# X3_Developer_RF.net
KiCad netlist of a schematic drawn in Altium Designer
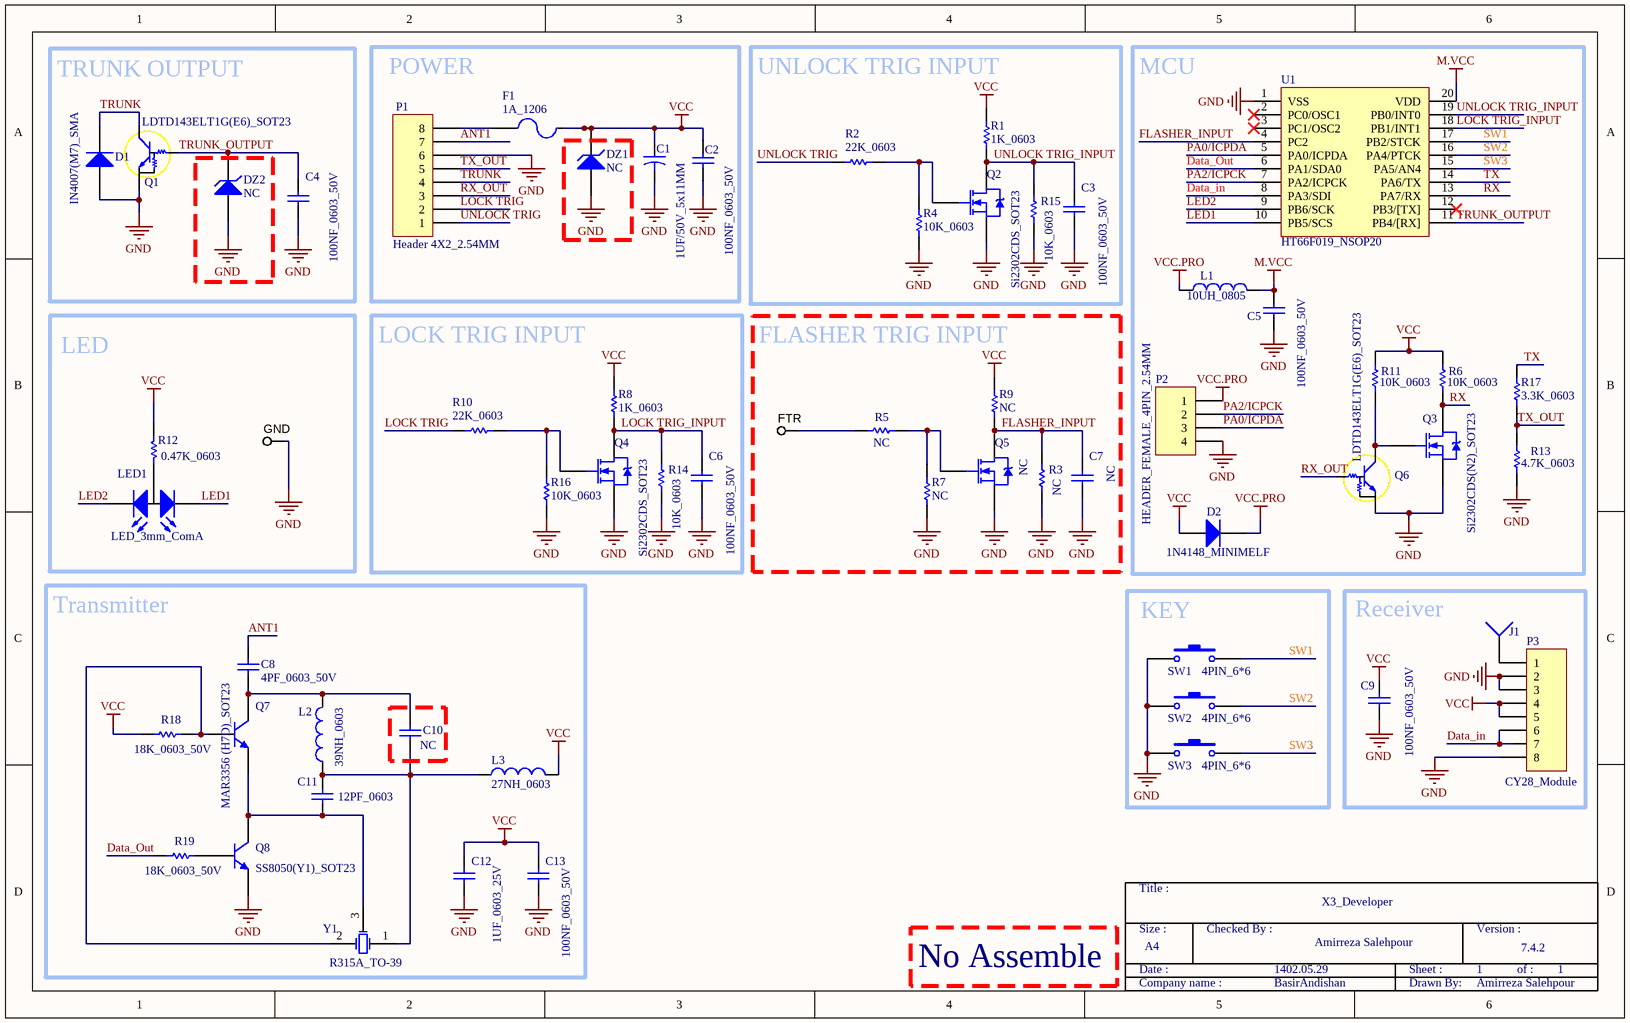
[diagram p0: X3_Developer_RF.SchDoc]

(export (version "E")
  (design (tool "Eeschema 10.0.6"))
  (components
    (comp (ref "C1")
      (value "1UF/50V_5x11MM")
      (footprint "Cap_5mm")
      (libsource (lib "Amir_Library") (part "Cap_Electrical"))
    )
    (comp (ref "C2")
      (value "100NF_0603_50V")
      (footprint "Cap_0603_Nominal")
      (libsource (lib "Saeed_New_Lib") (part "Cap"))
    )
    (comp (ref "C3")
      (value "100NF_0603_50V")
      (footprint "Cap_0603_Nominal")
      (libsource (lib "Saeed_New_Lib") (part "Cap"))
    )
    (comp (ref "C4")
      (value "100NF_0603_50V")
      (footprint "Cap_0603_Nominal")
      (libsource (lib "Saeed_New_Lib") (part "Cap"))
    )
    (comp (ref "C5")
      (value "100NF_0603_50V")
      (footprint "Cap_0603_Nominal")
      (libsource (lib "Saeed_New_Lib") (part "Cap"))
    )
    (comp (ref "C6")
      (value "100NF_0603_50V")
      (footprint "Cap_0603_Nominal")
      (libsource (lib "Saeed_New_Lib") (part "Cap"))
    )
    (comp (ref "C7")
      (value "NC")
      (footprint "Cap_0603_Nominal")
      (libsource (lib "Saeed_New_Lib") (part "Cap"))
    )
    (comp (ref "C8")
      (value "4PF_0603_50V")
      (footprint "Cap_0603_Nominal")
      (libsource (lib "Amir_Library") (part "Cap"))
    )
    (comp (ref "C9")
      (value "100NF_0603_50V")
      (footprint "Cap_0603_Nominal")
      (libsource (lib "Saeed_New_Lib") (part "Cap"))
    )
    (comp (ref "C10")
      (value "NC")
      (footprint "Cap_0603_Nominal")
      (libsource (lib "Amir_Library") (part "Cap"))
    )
    (comp (ref "C11")
      (value "12PF_0603")
      (footprint "Cap_0603_Nominal")
      (fields (field (name "Comment") "12PF_0603_50V"))
      (libsource (lib "Amir_Library") (part "Cap"))
    )
    (comp (ref "C12")
      (value "1UF_0603_25V")
      (footprint "Cap_0603_Nominal")
      (libsource (lib "Amir_Library") (part "Cap"))
    )
    (comp (ref "C13")
      (value "100NF_0603_50V")
      (footprint "Cap_0603_Nominal")
      (libsource (lib "Amir_Library") (part "Cap"))
    )
    (comp (ref "D1")
      (value "IN4007(M7)_SMA")
      (footprint "DIODE_SMA")
      (libsource (lib "My Shematic") (part "Diode"))
    )
    (comp (ref "D2")
      (value "1N4148_MINIMELF")
      (footprint "DIODE_MINIMELF")
      (libsource (lib "Amir_Library") (part "Diode"))
    )
    (comp (ref "DZ1")
      (value "NC")
      (footprint "Diode_ZENER_MINIMELF")
      (libsource (lib "Amir_Library") (part "Diode_Zener"))
    )
    (comp (ref "DZ2")
      (value "NC")
      (footprint "Diode_ZENER_MINIMELF")
      (libsource (lib "Amir_Library") (part "Diode_Zener"))
    )
    (comp (ref "F1")
      (value "1A_1206")
      (footprint "FUSE_1206_NOMINAL")
      (libsource (lib "Amir_Library") (part "FUSE"))
    )
    (comp (ref "FTR")
      (value "TESTPOINT_SMD")
      (footprint "TPSMD_D1")
      (fields (field (name "MANF") "MANF") (field (name "MANF_P#") "MANF_P#"))
      (libsource (lib "GTC Schematic") (part "TESTPOINT_SMD"))
    )
    (comp (ref "GND")
      (value "TESTPOINT_SMD")
      (footprint "TPSMD_D1")
      (fields (field (name "MANF") "MANF") (field (name "MANF_P#") "MANF_P#"))
      (libsource (lib "GTC Schematic") (part "TESTPOINT_SMD"))
    )
    (comp (ref "J1")
      (value "ANT")
      (footprint "PIN1")
      (description "Socket")
      (fields (field (name "PUBLISHER") "Altium Limited"))
      (libsource (lib "Miscellaneous Connectors") (part "Socket"))
    )
    (comp (ref "L1")
      (value "10UH_0805")
      (footprint "INDUCTOR_0805_Nominal")
      (libsource (lib "Saeed_New_Lib") (part "Inductor"))
    )
    (comp (ref "L2")
      (value "39NH_0603")
      (footprint "INDUCTOR_0603_NOMINAL")
      (libsource (lib "") (part "Inductor_1"))
    )
    (comp (ref "L3")
      (value "27NH_0603")
      (footprint "INDUCTOR_0603_NOMINAL")
      (libsource (lib "Amir_Library") (part "Inductor"))
    )
    (comp (ref "LED1")
      (value "LED_3mm_ComA")
      (footprint "LED_3mm_ComA")
      (libsource (lib "GTC Shem") (part "LED_ComA"))
    )
    (comp (ref "P1")
      (value "Header 4X2_2.54MM")
      (footprint "CON_2X4PIN")
      (description "Header, 4-Pin")
      (fields (field (name "PUBLISHER") "Altium Limited"))
      (libsource (lib "GTC Shem") (part "Header 8"))
    )
    (comp (ref "P2")
      (value "HEADER_FEMALE_4PIN_2.54MM")
      (footprint "HDR_F_1X4_2mm")
      (fields (field (name "PUBLISHER") "Altium Limited"))
      (libsource (lib "Miscellaneous Connectors") (part "Header 4"))
    )
    (comp (ref "P3")
      (value "CY28_Module")
      (footprint "RF_RXB6")
      (description "Receiver_315")
      (fields (field (name "PUBLISHER") "Altium Limited"))
      (libsource (lib "Amir_Library") (part "RXB6"))
    )
    (comp (ref "Q1")
      (value "LDTD143ELT1G(E6)_SOT23")
      (footprint "SOT23")
      (libsource (lib "My Shematic") (part "NPN_Digital"))
    )
    (comp (ref "Q2")
      (value "Si2302CDS_SOT23")
      (footprint "SOT23_MOSFET")
      (fields (field (name "PUBLISHER") "Altium Limited"))
      (libsource (lib "GTC Shem") (part "MOSFET_N"))
    )
    (comp (ref "Q3")
      (value "Si2302CDS(N2)_SOT23")
      (footprint "SOT23_MOSFET")
      (fields (field (name "PUBLISHER") "Altium Limited"))
      (libsource (lib "GTC Shem") (part "MOSFET_N"))
    )
    (comp (ref "Q4")
      (value "Si2302CDS_SOT23")
      (footprint "SOT23_MOSFET")
      (fields (field (name "PUBLISHER") "Altium Limited"))
      (libsource (lib "GTC Shem") (part "MOSFET_N"))
    )
    (comp (ref "Q5")
      (value "NC")
      (footprint "SOT23_MOSFET")
      (description "Si2302CDS_SOT23")
      (fields (field (name "PUBLISHER") "Altium Limited"))
      (libsource (lib "GTC Shem") (part "MOSFET_N"))
    )
    (comp (ref "Q6")
      (value "LDTD143ELT1G(E6)_SOT23")
      (footprint "SOT23")
      (libsource (lib "") (part "NPN_Digital_1"))
    )
    (comp (ref "Q7")
      (value "MAR3356 (H7D)_SOT23")
      (footprint "SOT23_BJT")
      (libsource (lib "Amir_Library") (part "NPN"))
    )
    (comp (ref "Q8")
      (value "SS8050(Y1)_SOT23")
      (footprint "SOT23_BJT")
      (libsource (lib "Amir_Library") (part "NPN"))
    )
    (comp (ref "R1")
      (value "1K_0603")
      (footprint "Res_0603_Nominal")
      (libsource (lib "My Shematic") (part "RES"))
    )
    (comp (ref "R2")
      (value "22K_0603")
      (footprint "Res_0603_Nominal")
      (libsource (lib "My Shematic") (part "RES"))
    )
    (comp (ref "R3") (value "NC") (footprint "Res_0603_Nominal") (libsource (lib "My Shematic") (part "RES")))
    (comp (ref "R4")
      (value "10K_0603")
      (footprint "Res_0603_Nominal")
      (libsource (lib "My Shematic") (part "RES"))
    )
    (comp (ref "R5") (value "NC") (footprint "Res_0603_Nominal") (libsource (lib "My Shematic") (part "RES")))
    (comp (ref "R6")
      (value "10K_0603")
      (footprint "Res_0603_Nominal")
      (libsource (lib "Amir_Library") (part "RES"))
    )
    (comp (ref "R7") (value "NC") (footprint "Res_0603_Nominal") (libsource (lib "My Shematic") (part "RES")))
    (comp (ref "R8")
      (value "1K_0603")
      (footprint "Res_0603_Nominal")
      (libsource (lib "My Shematic") (part "RES"))
    )
    (comp (ref "R9") (value "NC") (footprint "Res_0603_Nominal") (libsource (lib "My Shematic") (part "RES")))
    (comp (ref "R10")
      (value "22K_0603")
      (footprint "Res_0603_Nominal")
      (libsource (lib "My Shematic") (part "RES"))
    )
    (comp (ref "R11")
      (value "10K_0603")
      (footprint "Res_0603_Nominal")
      (libsource (lib "Amir_Library") (part "RES"))
    )
    (comp (ref "R12")
      (value "0.47K_0603")
      (footprint "Res_0603_Nominal")
      (libsource (lib "My Shematic") (part "RES"))
    )
    (comp (ref "R13")
      (value "4.7K_0603")
      (footprint "Res_0603_Nominal")
      (libsource (lib "Amir_Library") (part "RES"))
    )
    (comp (ref "R14")
      (value "10K_0603")
      (footprint "Res_0603_Nominal")
      (libsource (lib "My Shematic") (part "RES"))
    )
    (comp (ref "R15")
      (value "10K_0603")
      (footprint "Res_0603_Nominal")
      (libsource (lib "My Shematic") (part "RES"))
    )
    (comp (ref "R16")
      (value "10K_0603")
      (footprint "Res_0603_Nominal")
      (libsource (lib "My Shematic") (part "RES"))
    )
    (comp (ref "R17")
      (value "3.3K_0603")
      (footprint "Res_0603_Nominal")
      (libsource (lib "Amir_Library") (part "RES"))
    )
    (comp (ref "R18")
      (value "18K_0603_50V")
      (footprint "Res_0603_Nominal")
      (libsource (lib "Amir_Library") (part "RES"))
    )
    (comp (ref "R19")
      (value "18K_0603_50V")
      (footprint "Res_0603_Nominal")
      (libsource (lib "Amir_Library") (part "RES"))
    )
    (comp (ref "SW1")
      (value "4PIN_6*6")
      (footprint "SWITCH_DIP_6*6")
      (libsource (lib "My Shematic") (part "SW"))
    )
    (comp (ref "SW2")
      (value "4PIN_6*6")
      (footprint "SWITCH_DIP_6*6")
      (libsource (lib "Saeed_New_Lib") (part "SW_Right"))
    )
    (comp (ref "SW3")
      (value "4PIN_6*6")
      (footprint "SWITCH_DIP_6*6")
      (libsource (lib "Saeed_New_Lib") (part "SW_Right"))
    )
    (comp (ref "U1")
      (value "HT66F019_NSOP20")
      (footprint "NSOP20")
      (libsource (lib "GTC Shem") (part "HT66F019"))
    )
    (comp (ref "Y1")
      (value "R315A_TO-39")
      (footprint "CRYSTAL_TO39")
      (description "SAWFILTER")
      (libsource (lib "My Shematic") (part "Saw_Filter"))
    )
  )
  (nets
    (net (code "1") (name "/ANT1") (class "Default")
      (node (ref "C8") (pin "2") (pinfunction "2_2") (pintype "passive"))
      (node (ref "P1") (pin "7") (pinfunction "7_7") (pintype "passive"))
    )
    (net (code "2") (name "/Data_Out") (class "Default")
      (node (ref "R19") (pin "1") (pinfunction "1_1") (pintype "passive"))
      (node (ref "U1") (pin "6") (pinfunction "PA1/SDA0_6") (pintype "passive"))
    )
    (net (code "3") (name "/Data_in") (class "Default")
      (node (ref "P3") (pin "6") (pinfunction "6_6") (pintype "passive"))
      (node (ref "P3") (pin "7") (pinfunction "7_7") (pintype "passive"))
      (node (ref "U1") (pin "8") (pinfunction "PA3/SDI_8") (pintype "passive"))
    )
    (net (code "4") (name "/FLASHER_INPUT") (class "Default")
      (node (ref "C7") (pin "2") (pinfunction "2_2") (pintype "passive"))
      (node (ref "Q5") (pin "3") (pinfunction "D_3") (pintype "passive"))
      (node (ref "R3") (pin "1") (pinfunction "1_1") (pintype "passive"))
      (node (ref "R9") (pin "2") (pinfunction "2_2") (pintype "passive"))
      (node (ref "U1") (pin "4") (pinfunction "PC2_4") (pintype "passive"))
    )
    (net (code "5") (name "/LED1") (class "Default")
      (node (ref "LED1") (pin "2") (pinfunction "A2_2") (pintype "passive"))
      (node (ref "U1") (pin "10") (pinfunction "PB5/SCS_10") (pintype "passive"))
    )
    (net (code "6") (name "/LED2") (class "Default")
      (node (ref "LED1") (pin "1") (pinfunction "A1_1") (pintype "passive"))
      (node (ref "U1") (pin "9") (pinfunction "PB6/SCK_9") (pintype "passive"))
    )
    (net (code "7") (name "/LOCK TRIG") (class "Default")
      (node (ref "P1") (pin "2") (pinfunction "2_2") (pintype "passive"))
      (node (ref "R10") (pin "2") (pinfunction "2_2") (pintype "passive"))
    )
    (net (code "8") (name "/LOCK TRIG_INPUT") (class "Default")
      (node (ref "C6") (pin "2") (pinfunction "2_2") (pintype "passive"))
      (node (ref "Q4") (pin "3") (pinfunction "D_3") (pintype "passive"))
      (node (ref "R14") (pin "1") (pinfunction "1_1") (pintype "passive"))
      (node (ref "R8") (pin "2") (pinfunction "2_2") (pintype "passive"))
      (node (ref "U1") (pin "18") (pinfunction "PB1/INT1_18") (pintype "passive"))
    )
    (net (code "9") (name "/PA0{slash}ICPDA") (class "Default")
      (node (ref "P2") (pin "3") (pinfunction "3_3") (pintype "passive"))
      (node (ref "U1") (pin "5") (pinfunction "PA0/ICPDA_5") (pintype "passive"))
    )
    (net (code "10") (name "/PA2{slash}ICPCK") (class "Default")
      (node (ref "P2") (pin "2") (pinfunction "2_2") (pintype "passive"))
      (node (ref "U1") (pin "7") (pinfunction "PA2/ICPCK_7") (pintype "passive"))
    )
    (net (code "11") (name "/RX") (class "Default")
      (node (ref "Q3") (pin "3") (pinfunction "D_3") (pintype "passive"))
      (node (ref "R6") (pin "1") (pinfunction "1_1") (pintype "passive"))
      (node (ref "U1") (pin "13") (pinfunction "PA7/RX_13") (pintype "passive"))
    )
    (net (code "12") (name "/RX_OUT") (class "Default")
      (node (ref "P1") (pin "3") (pinfunction "3_3") (pintype "passive"))
      (node (ref "Q6") (pin "1") (pinfunction "B_1") (pintype "passive"))
    )
    (net (code "13") (name "/SW1") (class "Default")
      (node (ref "SW1") (pin "2") (pinfunction "2_2") (pintype "passive"))
      (node (ref "U1") (pin "17") (pinfunction "PB2/STCK_17") (pintype "passive"))
    )
    (net (code "14") (name "/SW2") (class "Default")
      (node (ref "SW2") (pin "2") (pinfunction "2_2") (pintype "passive"))
      (node (ref "U1") (pin "16") (pinfunction "PA4/PTCK_16") (pintype "passive"))
    )
    (net (code "15") (name "/SW3") (class "Default")
      (node (ref "SW3") (pin "2") (pinfunction "2_2") (pintype "passive"))
      (node (ref "U1") (pin "15") (pinfunction "PA5/AN4_15") (pintype "passive"))
    )
    (net (code "16") (name "/TRUNK") (class "Default")
      (node (ref "D1") (pin "2") (pinfunction "K_2") (pintype "passive"))
      (node (ref "P1") (pin "4") (pinfunction "4_4") (pintype "passive"))
      (node (ref "Q1") (pin "3") (pinfunction "C_3") (pintype "passive"))
    )
    (net (code "17") (name "/TRUNK_OUTPUT") (class "Default")
      (node (ref "C4") (pin "2") (pinfunction "2_2") (pintype "passive"))
      (node (ref "DZ2") (pin "2") (pinfunction "K_2") (pintype "passive"))
      (node (ref "Q1") (pin "1") (pinfunction "B_1") (pintype "passive"))
      (node (ref "U1") (pin "11") (pinfunction "PB4/[RX]_11") (pintype "passive"))
    )
    (net (code "18") (name "/TX") (class "Default")
      (node (ref "R17") (pin "1") (pinfunction "1_1") (pintype "passive"))
      (node (ref "U1") (pin "14") (pinfunction "PA6/TX_14") (pintype "passive"))
    )
    (net (code "19") (name "/TX_OUT") (class "Default")
      (node (ref "P1") (pin "5") (pinfunction "5_5") (pintype "passive"))
      (node (ref "R13") (pin "2") (pinfunction "2_2") (pintype "passive"))
      (node (ref "R17") (pin "2") (pinfunction "2_2") (pintype "passive"))
    )
    (net (code "20") (name "/UNLOCK TRIG") (class "Default")
      (node (ref "P1") (pin "1") (pinfunction "1_1") (pintype "passive"))
      (node (ref "R2") (pin "2") (pinfunction "2_2") (pintype "passive"))
    )
    (net (code "21") (name "/UNLOCK TRIG_INPUT") (class "Default")
      (node (ref "C3") (pin "2") (pinfunction "2_2") (pintype "passive"))
      (node (ref "Q2") (pin "3") (pinfunction "D_3") (pintype "passive"))
      (node (ref "R1") (pin "2") (pinfunction "2_2") (pintype "passive"))
      (node (ref "R15") (pin "1") (pinfunction "1_1") (pintype "passive"))
      (node (ref "U1") (pin "19") (pinfunction "PB0/INT0_19") (pintype "passive"))
    )
    (net (code "22") (name "GND") (class "Default")
      (node (ref "C1") (pin "2") (pinfunction "2_2") (pintype "passive"))
      (node (ref "C12") (pin "1") (pinfunction "1_1") (pintype "passive"))
      (node (ref "C13") (pin "1") (pinfunction "1_1") (pintype "passive"))
      (node (ref "C2") (pin "1") (pinfunction "1_1") (pintype "passive"))
      (node (ref "C3") (pin "1") (pinfunction "1_1") (pintype "passive"))
      (node (ref "C4") (pin "1") (pinfunction "1_1") (pintype "passive"))
      (node (ref "C5") (pin "1") (pinfunction "1_1") (pintype "passive"))
      (node (ref "C6") (pin "1") (pinfunction "1_1") (pintype "passive"))
      (node (ref "C7") (pin "1") (pinfunction "1_1") (pintype "passive"))
      (node (ref "C9") (pin "1") (pinfunction "1_1") (pintype "passive"))
      (node (ref "D1") (pin "1") (pinfunction "A_1") (pintype "passive"))
      (node (ref "DZ1") (pin "1") (pinfunction "A_1") (pintype "passive"))
      (node (ref "DZ2") (pin "1") (pinfunction "A_1") (pintype "passive"))
      (node (ref "GND") (pin "1") (pinfunction "1_1") (pintype "passive"))
      (node (ref "P1") (pin "6") (pinfunction "6_6") (pintype "passive"))
      (node (ref "P2") (pin "4") (pinfunction "4_4") (pintype "passive"))
      (node (ref "P3") (pin "2") (pinfunction "2_2") (pintype "passive"))
      (node (ref "P3") (pin "3") (pinfunction "3_3") (pintype "passive"))
      (node (ref "P3") (pin "8") (pinfunction "8_8") (pintype "passive"))
      (node (ref "Q1") (pin "2") (pinfunction "E_2") (pintype "passive"))
      (node (ref "Q2") (pin "2") (pinfunction "S_2") (pintype "passive"))
      (node (ref "Q3") (pin "2") (pinfunction "S_2") (pintype "passive"))
      (node (ref "Q4") (pin "2") (pinfunction "S_2") (pintype "passive"))
      (node (ref "Q5") (pin "2") (pinfunction "S_2") (pintype "passive"))
      (node (ref "Q6") (pin "2") (pinfunction "E_2") (pintype "passive"))
      (node (ref "Q8") (pin "2") (pinfunction "E_2") (pintype "passive"))
      (node (ref "R13") (pin "1") (pinfunction "1_1") (pintype "passive"))
      (node (ref "R14") (pin "2") (pinfunction "2_2") (pintype "passive"))
      (node (ref "R15") (pin "2") (pinfunction "2_2") (pintype "passive"))
      (node (ref "R16") (pin "2") (pinfunction "2_2") (pintype "passive"))
      (node (ref "R3") (pin "2") (pinfunction "2_2") (pintype "passive"))
      (node (ref "R4") (pin "2") (pinfunction "2_2") (pintype "passive"))
      (node (ref "R7") (pin "2") (pinfunction "2_2") (pintype "passive"))
      (node (ref "SW1") (pin "1") (pinfunction "1_1") (pintype "passive"))
      (node (ref "SW2") (pin "1") (pinfunction "1_1") (pintype "passive"))
      (node (ref "SW3") (pin "1") (pinfunction "1_1") (pintype "passive"))
      (node (ref "U1") (pin "1") (pinfunction "VSS_1") (pintype "passive"))
    )
    (net (code "23") (name "M.VCC") (class "Default")
      (node (ref "C5") (pin "2") (pinfunction "2_2") (pintype "passive"))
      (node (ref "L1") (pin "2") (pinfunction "2_2") (pintype "passive"))
      (node (ref "U1") (pin "20") (pinfunction "VDD_20") (pintype "passive"))
    )
    (net (code "24") (name "Net-(C10-Pad1)") (class "Default")
      (node (ref "C10") (pin "1") (pinfunction "1_1") (pintype "passive"))
      (node (ref "C11") (pin "2") (pinfunction "2_2") (pintype "passive"))
      (node (ref "L2") (pin "1") (pinfunction "1_1") (pintype "passive"))
      (node (ref "L3") (pin "2") (pinfunction "2_2") (pintype "passive"))
      (node (ref "Y1") (pin "1") (pinfunction "1_1") (pintype "passive"))
    )
    (net (code "25") (name "Net-(F1-Pad1)") (class "Default")
      (node (ref "F1") (pin "1") (pinfunction "1_1") (pintype "passive"))
      (node (ref "P1") (pin "8") (pinfunction "8_8") (pintype "passive"))
    )
    (net (code "26") (name "Net-(FTR-Pad1)") (class "Default")
      (node (ref "FTR") (pin "1") (pinfunction "1_1") (pintype "passive"))
      (node (ref "R5") (pin "2") (pinfunction "2_2") (pintype "passive"))
    )
    (net (code "27") (name "Net-(J1-Pad1)") (class "Default")
      (node (ref "J1") (pin "1") (pinfunction "1_1") (pintype "passive"))
      (node (ref "P3") (pin "1") (pinfunction "1_1") (pintype "passive"))
    )
    (net (code "28") (name "Net-(LED1-K)") (class "Default")
      (node (ref "LED1") (pin "3") (pinfunction "K_3") (pintype "passive"))
      (node (ref "R12") (pin "2") (pinfunction "2_2") (pintype "passive"))
    )
    (net (code "29") (name "Net-(Q2-G)") (class "Default")
      (node (ref "Q2") (pin "1") (pinfunction "G_1") (pintype "passive"))
      (node (ref "R2") (pin "1") (pinfunction "1_1") (pintype "passive"))
      (node (ref "R4") (pin "1") (pinfunction "1_1") (pintype "passive"))
    )
    (net (code "30") (name "Net-(Q3-G)") (class "Default")
      (node (ref "Q3") (pin "1") (pinfunction "G_1") (pintype "passive"))
      (node (ref "Q6") (pin "3") (pinfunction "C_3") (pintype "passive"))
      (node (ref "R11") (pin "1") (pinfunction "1_1") (pintype "passive"))
    )
    (net (code "31") (name "Net-(Q4-G)") (class "Default")
      (node (ref "Q4") (pin "1") (pinfunction "G_1") (pintype "passive"))
      (node (ref "R10") (pin "1") (pinfunction "1_1") (pintype "passive"))
      (node (ref "R16") (pin "1") (pinfunction "1_1") (pintype "passive"))
    )
    (net (code "32") (name "Net-(Q5-G)") (class "Default")
      (node (ref "Q5") (pin "1") (pinfunction "G_1") (pintype "passive"))
      (node (ref "R5") (pin "1") (pinfunction "1_1") (pintype "passive"))
      (node (ref "R7") (pin "1") (pinfunction "1_1") (pintype "passive"))
    )
    (net (code "33") (name "Net-(Q7-B)") (class "Default")
      (node (ref "Q7") (pin "1") (pinfunction "B_1") (pintype "passive"))
      (node (ref "R18") (pin "1") (pinfunction "1_1") (pintype "passive"))
      (node (ref "Y1") (pin "2") (pinfunction "2_2") (pintype "passive"))
    )
    (net (code "34") (name "Net-(Q7-C)") (class "Default")
      (node (ref "C10") (pin "2") (pinfunction "2_2") (pintype "passive"))
      (node (ref "C8") (pin "1") (pinfunction "1_1") (pintype "passive"))
      (node (ref "L2") (pin "2") (pinfunction "2_2") (pintype "passive"))
      (node (ref "Q7") (pin "3") (pinfunction "C_3") (pintype "passive"))
    )
    (net (code "35") (name "Net-(Q7-E)") (class "Default")
      (node (ref "C11") (pin "1") (pinfunction "1_1") (pintype "passive"))
      (node (ref "Q7") (pin "2") (pinfunction "E_2") (pintype "passive"))
      (node (ref "Q8") (pin "3") (pinfunction "C_3") (pintype "passive"))
      (node (ref "Y1") (pin "3") (pinfunction "3_3") (pintype "passive"))
    )
    (net (code "36") (name "Net-(Q8-B)") (class "Default")
      (node (ref "Q8") (pin "1") (pinfunction "B_1") (pintype "passive"))
      (node (ref "R19") (pin "2") (pinfunction "2_2") (pintype "passive"))
    )
    (net (code "37") (name "VCC") (class "Default")
      (node (ref "C1") (pin "1") (pinfunction "1_1") (pintype "passive"))
      (node (ref "C12") (pin "2") (pinfunction "2_2") (pintype "passive"))
      (node (ref "C13") (pin "2") (pinfunction "2_2") (pintype "passive"))
      (node (ref "C2") (pin "2") (pinfunction "2_2") (pintype "passive"))
      (node (ref "C9") (pin "2") (pinfunction "2_2") (pintype "passive"))
      (node (ref "D2") (pin "1") (pinfunction "A_1") (pintype "passive"))
      (node (ref "DZ1") (pin "2") (pinfunction "K_2") (pintype "passive"))
      (node (ref "F1") (pin "2") (pinfunction "2_2") (pintype "passive"))
      (node (ref "L3") (pin "1") (pinfunction "1_1") (pintype "passive"))
      (node (ref "P3") (pin "4") (pinfunction "4_4") (pintype "passive"))
      (node (ref "P3") (pin "5") (pinfunction "5_5") (pintype "passive"))
      (node (ref "R1") (pin "1") (pinfunction "1_1") (pintype "passive"))
      (node (ref "R11") (pin "2") (pinfunction "2_2") (pintype "passive"))
      (node (ref "R12") (pin "1") (pinfunction "1_1") (pintype "passive"))
      (node (ref "R18") (pin "2") (pinfunction "2_2") (pintype "passive"))
      (node (ref "R6") (pin "2") (pinfunction "2_2") (pintype "passive"))
      (node (ref "R8") (pin "1") (pinfunction "1_1") (pintype "passive"))
      (node (ref "R9") (pin "1") (pinfunction "1_1") (pintype "passive"))
    )
    (net (code "38") (name "VCC.PRO") (class "Default")
      (node (ref "D2") (pin "2") (pinfunction "K_2") (pintype "passive"))
      (node (ref "L1") (pin "1") (pinfunction "1_1") (pintype "passive"))
      (node (ref "P2") (pin "1") (pinfunction "1_1") (pintype "passive"))
    )
    (net (code "39") (name "unconnected-(U1-PB3{slash}[TX]-Pad12)") (class "Default")
      (node (ref "U1") (pin "12") (pinfunction "PB3/[TX]_12") (pintype "passive+no_connect"))
    )
    (net (code "40") (name "unconnected-(U1-PC0{slash}OSC1-Pad2)") (class "Default")
      (node (ref "U1") (pin "2") (pinfunction "PC0/OSC1_2") (pintype "passive+no_connect"))
    )
    (net (code "41") (name "unconnected-(U1-PC1{slash}OSC2-Pad3)") (class "Default")
      (node (ref "U1") (pin "3") (pinfunction "PC1/OSC2_3") (pintype "passive+no_connect"))
    )
  )
)
